# Grove_-_DMX512_v1_0.net
KiCad netlist of a schematic drawn in EAGLE
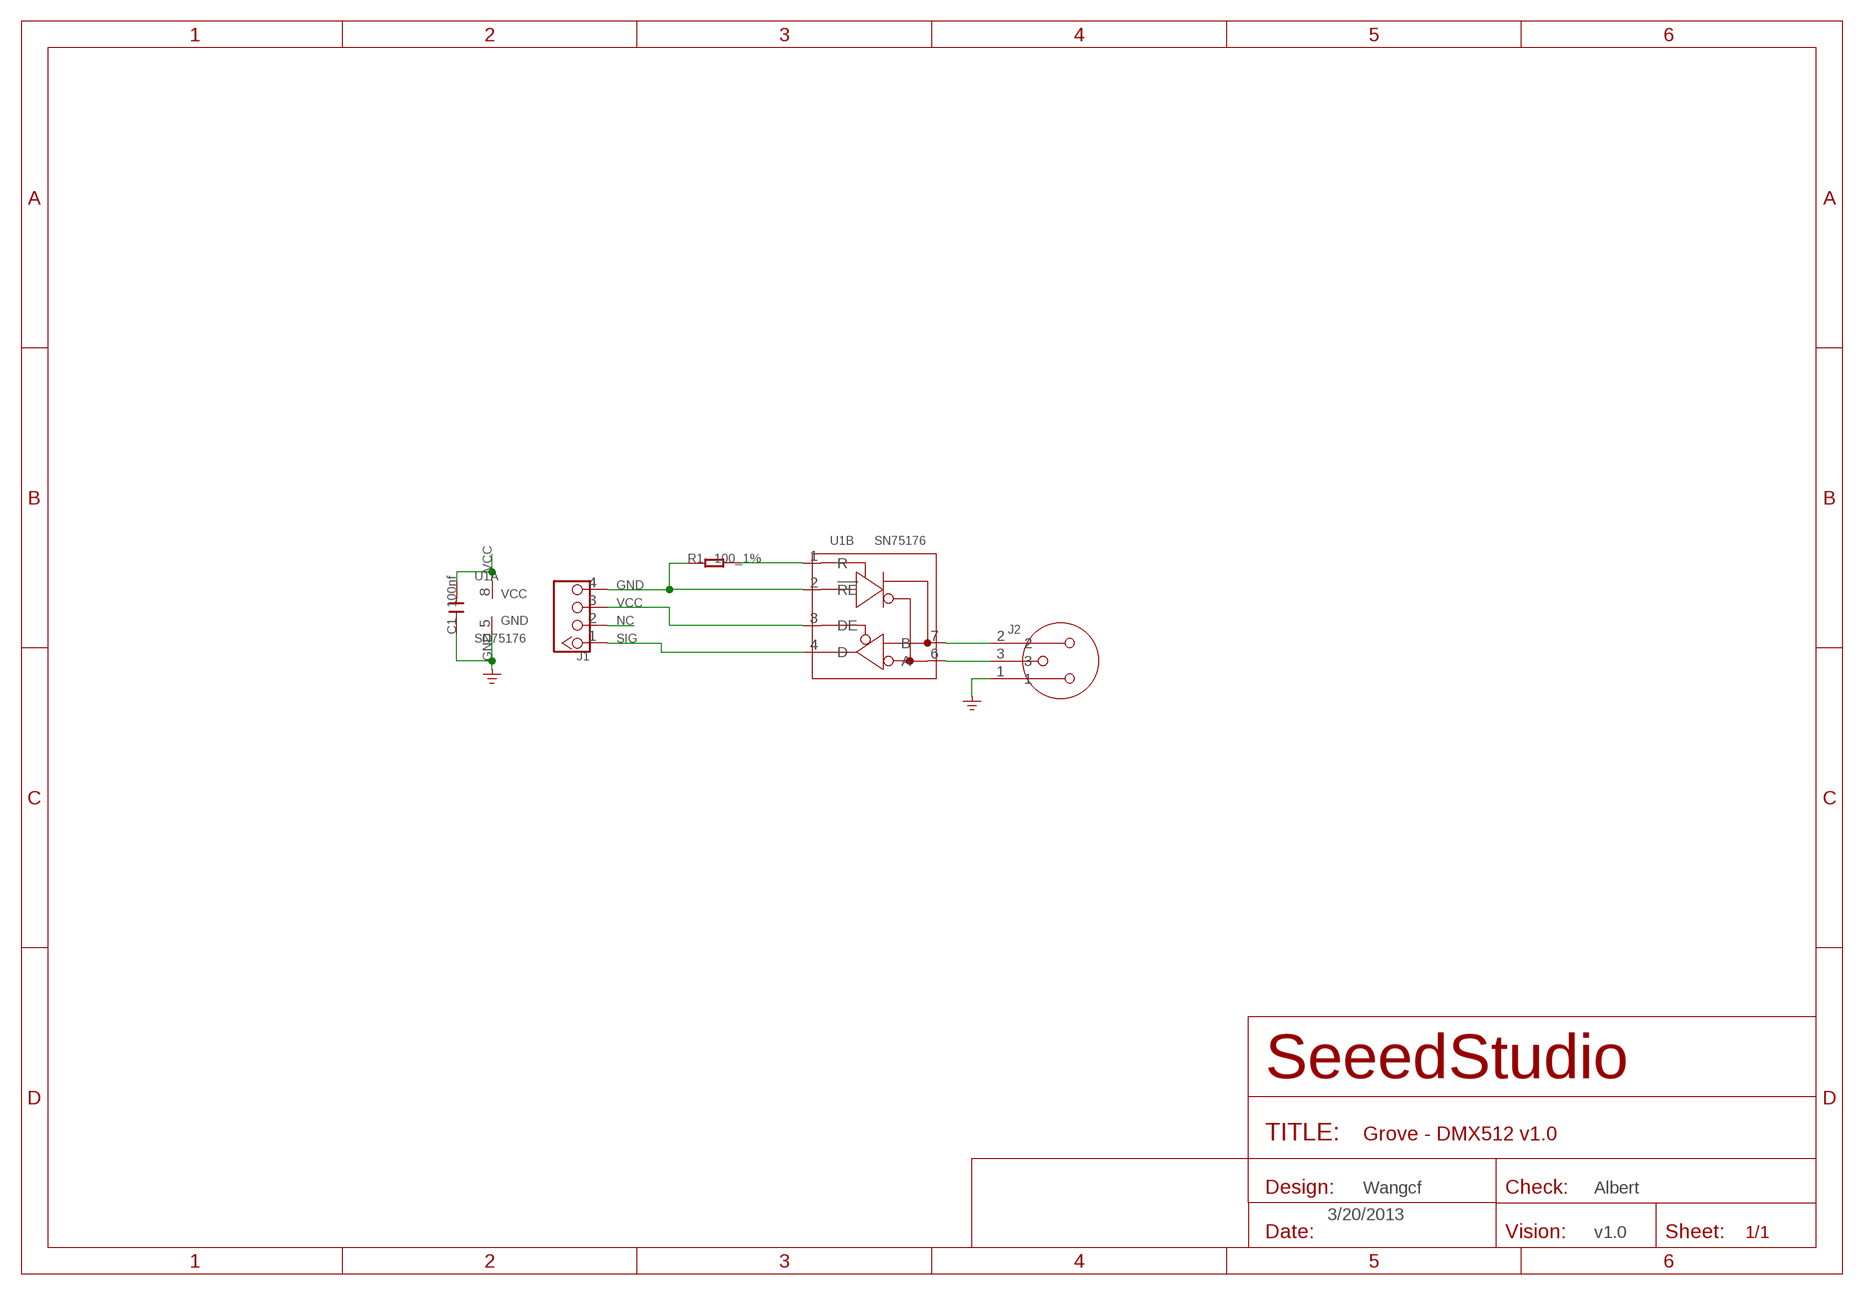
[diagram p0: schematic, sheet 1]

(export (version "E")
  (design (tool "Eeschema 10.0.6"))
  (components
    (comp (ref "C1")
      (value "100nf")
      (footprint "eagle-import:C0603")
      (libsource (lib "eagle-import") (part "C-0603"))
    )
    (comp (ref "J1")
      (value "TWIG-4P-2.0-2.0")
      (footprint "eagle-import:4P-2.0")
      (libsource (lib "eagle-import") (part "TWIG-4P-2.0-2.0"))
    )
    (comp (ref "J2")
      (value "H22")
      (footprint "eagle-import:3P-4.0")
      (libsource (lib "eagle-import") (part "H22"))
    )
    (comp (ref "R1")
      (value "100_1%")
      (footprint "eagle-import:R0603")
      (libsource (lib "eagle-import") (part "R-0603"))
    )
    (comp (ref "U1")
      (value "SN75176")
      (footprint "eagle-import:SOIC8")
      (libsource (lib "eagle-import") (part "SN75176'ADR'"))
    )
  )
  (nets
    (net (code "1") (name "/NC") (class "Default")
      (node (ref "J1") (pin "2") (pinfunction "2_2") (pintype "bidirectional"))
    )
    (net (code "2") (name "/SIG") (class "Default")
      (node (ref "J1") (pin "1") (pinfunction "1_1") (pintype "bidirectional"))
      (node (ref "U1") (pin "4") (pinfunction "D_4") (pintype "bidirectional"))
    )
    (net (code "3") (name "/VCC") (class "Default")
      (node (ref "C1") (pin "2") (pinfunction "2_2") (pintype "passive"))
      (node (ref "J1") (pin "3") (pinfunction "3_3") (pintype "bidirectional"))
      (node (ref "U1") (pin "3") (pinfunction "DE_3") (pintype "bidirectional"))
      (node (ref "U1") (pin "8") (pinfunction "VCC_8") (pintype "bidirectional"))
    )
    (net (code "4") (name "GND_POWER") (class "Default")
      (node (ref "C1") (pin "1") (pinfunction "1_1") (pintype "passive"))
      (node (ref "J1") (pin "4") (pinfunction "4_4") (pintype "bidirectional"))
      (node (ref "J2") (pin "1") (pinfunction "1_1") (pintype "bidirectional"))
      (node (ref "R1") (pin "1") (pinfunction "1_1") (pintype "passive"))
      (node (ref "U1") (pin "2") (pinfunction "~{RE}_2") (pintype "bidirectional"))
      (node (ref "U1") (pin "5") (pinfunction "GND_5") (pintype "bidirectional"))
    )
    (net (code "5") (name "Net-(U1B-A)") (class "Default")
      (node (ref "J2") (pin "3") (pinfunction "3_3") (pintype "bidirectional"))
      (node (ref "U1") (pin "6") (pinfunction "A_6") (pintype "bidirectional"))
    )
    (net (code "6") (name "Net-(U1B-B)") (class "Default")
      (node (ref "J2") (pin "2") (pinfunction "2_2") (pintype "bidirectional"))
      (node (ref "U1") (pin "7") (pinfunction "B_7") (pintype "bidirectional"))
    )
    (net (code "7") (name "Net-(U1B-R)") (class "Default")
      (node (ref "R1") (pin "2") (pinfunction "2_2") (pintype "passive"))
      (node (ref "U1") (pin "1") (pinfunction "R_1") (pintype "bidirectional"))
    )
  )
)
